# SSFocuser-B-TMC2208-O.net
KiCad netlist of a schematic drawn in Altium Designer
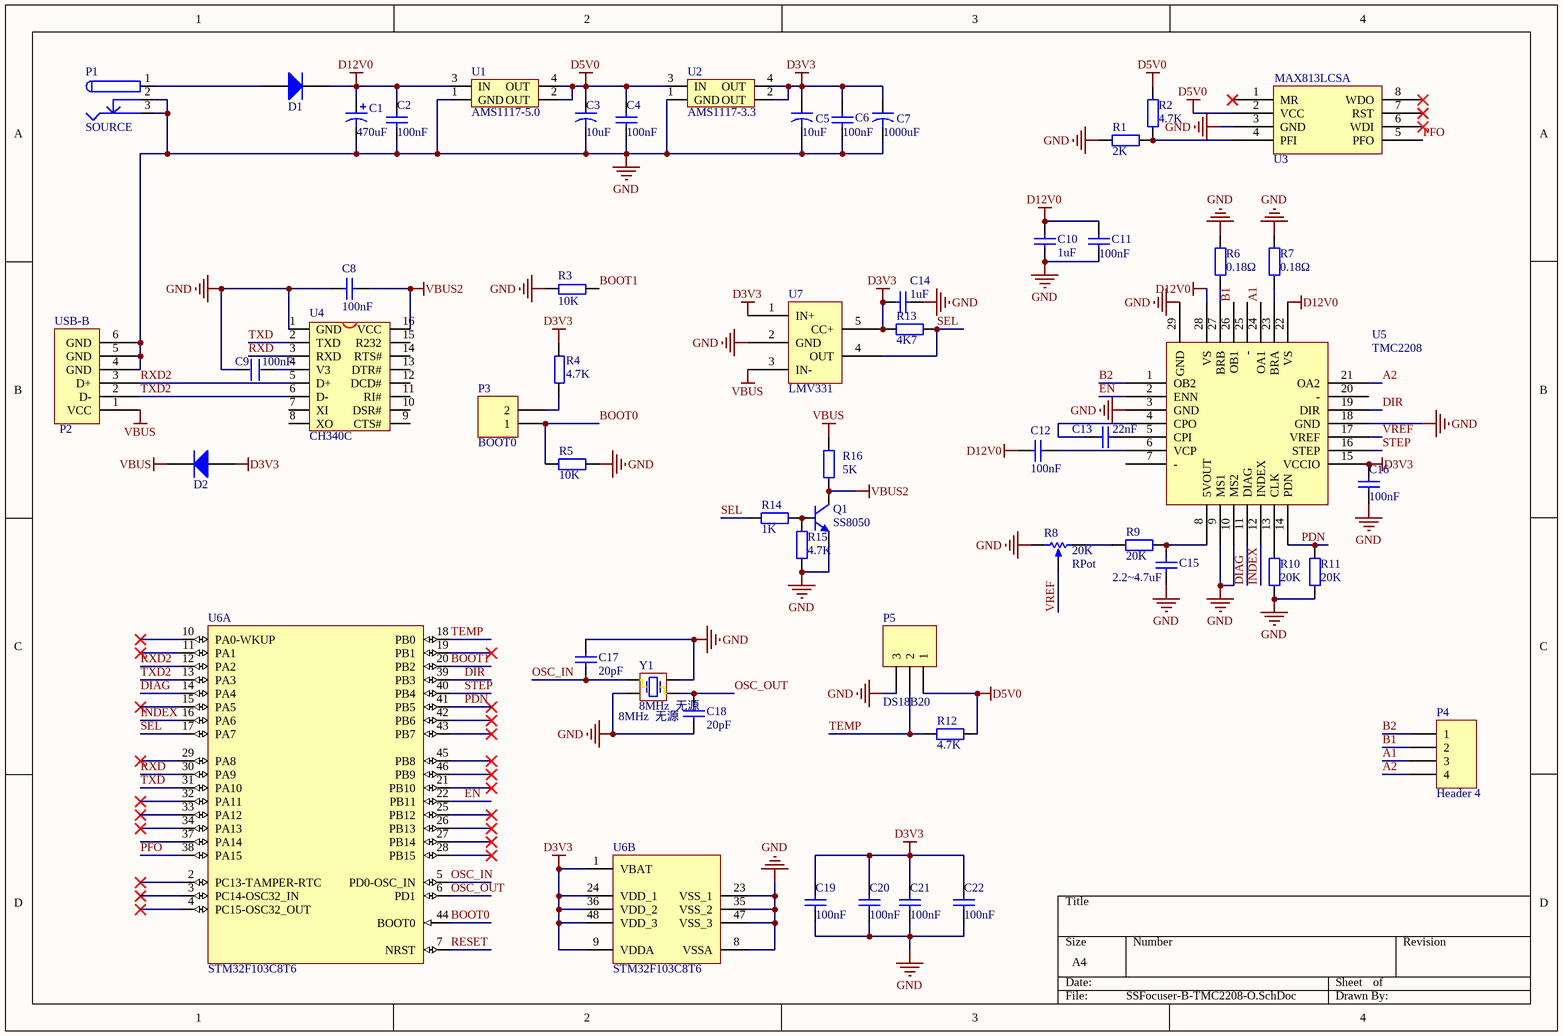
[diagram p0: SSFocuser-B-TMC2208-O.SchDoc]

(export (version "E")
  (design (tool "Eeschema 10.0.6"))
  (components
    (comp (ref "C1")
      (value "470uF")
      (footprint "16V/470U(CD10X10D5)")
      (description "470UF      16V      CD10X10D5")
      (libsource (lib "平台原理图symbol图库V1.0") (part "C470UF016S"))
    )
    (comp (ref "C2")
      (value "100nF")
      (footprint "0603C")
      (description "Capacitor")
      (fields (field (name "PUBLISHER") "Altium Limited"))
      (libsource (lib "Crazy_PCB") (part "Cap"))
    )
    (comp (ref "C3")
      (value "10uF")
      (footprint "3216")
      (fields (field (name "VAULE") "10uF"))
      (libsource (lib "Crazy_PCB") (part "CAP2"))
    )
    (comp (ref "C4")
      (value "100nF")
      (footprint "0603C")
      (description "Capacitor")
      (fields (field (name "PUBLISHER") "Altium Limited"))
      (libsource (lib "Crazy_PCB") (part "Cap"))
    )
    (comp (ref "C5")
      (value "10uF")
      (footprint "3216")
      (fields (field (name "VAULE") "10uF"))
      (libsource (lib "Crazy_PCB") (part "CAP2"))
    )
    (comp (ref "C6")
      (value "100nF")
      (footprint "0603C")
      (description "Capacitor")
      (fields (field (name "PUBLISHER") "Altium Limited"))
      (libsource (lib "Crazy_PCB") (part "Cap"))
    )
    (comp (ref "C7")
      (value "1000uF")
      (footprint "16V/470U(CD10X10D5)")
      (fields (field (name "VAULE") "1000uF"))
      (libsource (lib "Crazy_PCB") (part "CAP2"))
    )
    (comp (ref "C8")
      (value "100nF")
      (footprint "0603C")
      (description "Capacitor")
      (fields (field (name "PUBLISHER") "Altium Limited"))
      (libsource (lib "Crazy_PCB") (part "Cap"))
    )
    (comp (ref "C9")
      (value "100nF")
      (footprint "0603C")
      (libsource (lib "WarShip V3 STM32103封装库") (part "C"))
    )
    (comp (ref "C10")
      (value "1uF")
      (footprint "1206C")
      (description "Capacitor")
      (fields (field (name "PUBLISHER") "Altium Limited"))
      (libsource (lib "Crazy_PCB") (part "Cap"))
    )
    (comp (ref "C11")
      (value "100nF")
      (footprint "0603C")
      (description "Capacitor")
      (fields (field (name "PUBLISHER") "Altium Limited"))
      (libsource (lib "Crazy_PCB") (part "Cap"))
    )
    (comp (ref "C12")
      (value "100nF")
      (footprint "0603C")
      (description "Capacitor")
      (fields (field (name "PUBLISHER") "Altium Limited"))
      (libsource (lib "Crazy_PCB") (part "Cap"))
    )
    (comp (ref "C13")
      (value "22nF")
      (footprint "0603C")
      (description "Capacitor")
      (fields (field (name "PUBLISHER") "Altium Limited"))
      (libsource (lib "Crazy_PCB") (part "Cap"))
    )
    (comp (ref "C14")
      (value "1uF")
      (footprint "0603C")
      (description "Capacitor")
      (fields (field (name "PUBLISHER") "Altium Limited"))
      (libsource (lib "Crazy_PCB") (part "Cap"))
    )
    (comp (ref "C15")
      (value "2.2~4.7uF")
      (footprint "0603C")
      (description "Capacitor")
      (fields (field (name "PUBLISHER") "Altium Limited"))
      (libsource (lib "Crazy_PCB") (part "Cap"))
    )
    (comp (ref "C16")
      (value "100nF")
      (footprint "0603C")
      (description "Capacitor")
      (fields (field (name "PUBLISHER") "Altium Limited"))
      (libsource (lib "Crazy_PCB") (part "Cap"))
    )
    (comp (ref "C17")
      (value "20pF")
      (footprint "0603C")
      (description "Capacitor")
      (fields (field (name "PUBLISHER") "Altium Limited"))
      (libsource (lib "JL_SCH") (part "Cap"))
    )
    (comp (ref "C18")
      (value "20pF")
      (footprint "0603C")
      (description "Capacitor")
      (fields (field (name "PUBLISHER") "Altium Limited"))
      (libsource (lib "JL_SCH") (part "Cap"))
    )
    (comp (ref "C19")
      (value "100nF")
      (footprint "0603C")
      (description "Capacitor")
      (fields (field (name "PUBLISHER") "Altium Limited"))
      (libsource (lib "Crazy_PCB") (part "Cap"))
    )
    (comp (ref "C20")
      (value "100nF")
      (footprint "0603C")
      (description "Capacitor")
      (fields (field (name "PUBLISHER") "Altium Limited"))
      (libsource (lib "Crazy_PCB") (part "Cap"))
    )
    (comp (ref "C21")
      (value "100nF")
      (footprint "0603C")
      (description "Capacitor")
      (fields (field (name "PUBLISHER") "Altium Limited"))
      (libsource (lib "Crazy_PCB") (part "Cap"))
    )
    (comp (ref "C22")
      (value "100nF")
      (footprint "0603C")
      (description "Capacitor")
      (fields (field (name "PUBLISHER") "Altium Limited"))
      (libsource (lib "Crazy_PCB") (part "Cap"))
    )
    (comp (ref "D1")
      (value "M7")
      (footprint "DO-214AC")
      (description "High Conductance Fast Diode")
      (fields (field (name "PUBLISHER") "Altium Limited"))
      (libsource (lib "Crazy_PCB") (part "Diode"))
    )
    (comp (ref "D2")
      (value "M7")
      (footprint "DO-214AC")
      (description "High Conductance Fast Diode")
      (fields (field (name "PUBLISHER") "Altium Limited"))
      (libsource (lib "Crazy_PCB") (part "Diode"))
    )
    (comp (ref "P1")
      (value "SOURCE")
      (footprint "DC005")
      (fields (field (name "PUBLISHER") "Altium Limited"))
      (libsource (lib "Crazy_PCB") (part "SOURCE"))
    )
    (comp (ref "P2") (value "USB-B") (footprint "USB-B") (libsource (lib "DX") (part "USB-B")))
    (comp (ref "P3")
      (value "BOOT0")
      (footprint "HDR1X2")
      (description "Header, 2-Pin")
      (fields (field (name "PUBLISHER") "Altium Limited"))
      (libsource (lib "Miscellaneous Connectors") (part "MHDR1X2"))
    )
    (comp (ref "P4")
      (value "Header 4")
      (footprint "XH_4_V")
      (description "Header, 4-Pin")
      (fields (field (name "PUBLISHER") "Altium Limited"))
      (libsource (lib "Miscellaneous Connectors") (part "Header 4"))
    )
    (comp (ref "P5")
      (value "DS18B20")
      (footprint "TO-92B")
      (description "Header, 3-Pin")
      (fields (field (name "PUBLISHER") "Altium Limited"))
      (libsource (lib "Miscellaneous Connectors") (part "Header 3"))
    )
    (comp (ref "Q1")
      (value "SS8050")
      (footprint "SOT23-3M")
      (description "高频放大-NPN型")
      (fields (field (name "版权归属") "源创客"))
      (libsource (lib "6.2   - 三极管") (part "8050-SMD"))
    )
    (comp (ref "R1")
      (value "2K")
      (footprint "0603R")
      (description "Resistor")
      (fields (field (name "PUBLISHER") "Altium Limited"))
      (libsource (lib "Crazy_PCB") (part "RES"))
    )
    (comp (ref "R2")
      (value "4.7K")
      (footprint "0603R")
      (description "Resistor")
      (fields (field (name "PUBLISHER") "Altium Limited"))
      (libsource (lib "") (part "RES_1"))
    )
    (comp (ref "R3") (value "10K") (footprint "0603R") (libsource (lib "WarShip V3 STM32103封装库") (part "R")))
    (comp (ref "R4") (value "4.7K") (footprint "0603R") (libsource (lib "WarShip V3 STM32103封装库") (part "R")))
    (comp (ref "R5")
      (value "10K")
      (footprint "0603R")
      (description "Resistor")
      (fields (field (name "PUBLISHER") "Altium Limited"))
      (libsource (lib "") (part "RES_2"))
    )
    (comp (ref "R6")
      (value "0.18Ω")
      (footprint "1206R")
      (description "Resistor")
      (fields (field (name "PUBLISHER") "Altium Limited"))
      (libsource (lib "") (part "RES_3"))
    )
    (comp (ref "R7")
      (value "0.18Ω")
      (footprint "1206R")
      (description "Resistor")
      (fields (field (name "PUBLISHER") "Altium Limited"))
      (libsource (lib "") (part "RES_3"))
    )
    (comp (ref "R8")
      (value "RPot")
      (footprint "VR_SMD")
      (description "Potentiometer")
      (fields (field (name "ALTIUM_VALUE") "20K") (field (name "PUBLISHER") "Altium Limited"))
      (libsource (lib "Miscellaneous Devices") (part "RPot"))
    )
    (comp (ref "R9")
      (value "20K")
      (footprint "0603R")
      (description "Resistor")
      (fields (field (name "PUBLISHER") "Altium Limited"))
      (libsource (lib "Crazy_PCB") (part "RES"))
    )
    (comp (ref "R10")
      (value "20K")
      (footprint "0603R")
      (description "Resistor")
      (fields (field (name "PUBLISHER") "Altium Limited"))
      (libsource (lib "") (part "RES_1"))
    )
    (comp (ref "R11")
      (value "20K")
      (footprint "0603R")
      (description "Resistor")
      (fields (field (name "PUBLISHER") "Altium Limited"))
      (libsource (lib "") (part "RES_1"))
    )
    (comp (ref "R12")
      (value "4.7K")
      (footprint "0603R")
      (description "Resistor")
      (fields (field (name "PUBLISHER") "Altium Limited"))
      (libsource (lib "") (part "RES_2"))
    )
    (comp (ref "R13")
      (value "4K7")
      (footprint "0603R")
      (description "Resistor")
      (fields (field (name "PUBLISHER") "Altium Limited"))
      (libsource (lib "Crazy_PCB") (part "RES"))
    )
    (comp (ref "R14")
      (value "1K")
      (footprint "0603R")
      (description "Resistor")
      (fields (field (name "PUBLISHER") "Altium Limited"))
      (libsource (lib "Crazy_PCB") (part "RES"))
    )
    (comp (ref "R15")
      (value "4.7K")
      (footprint "0603R")
      (description "Resistor")
      (fields (field (name "PUBLISHER") "Altium Limited"))
      (libsource (lib "") (part "RES_3"))
    )
    (comp (ref "R16")
      (value "5K")
      (footprint "0603R")
      (description "Resistor")
      (fields (field (name "PUBLISHER") "Altium Limited"))
      (libsource (lib "") (part "RES_3"))
    )
    (comp (ref "U1")
      (value "AMS1117-5.0")
      (footprint "SOT223")
      (libsource (lib "MiniSTM32 V3.0封装库") (part "AMS1117"))
    )
    (comp (ref "U2")
      (value "AMS1117-3.3")
      (footprint "SOT223")
      (libsource (lib "MiniSTM32 V3.0封装库") (part "AMS1117"))
    )
    (comp (ref "U3") (value "MAX813LCSA") (footprint "SOP-8") (libsource (lib "DX") (part "MAX813L")))
    (comp (ref "U4")
      (value "CH340C")
      (footprint "SO-16")
      (description "USB2UART")
      (libsource (lib "WarShip V3 STM32103封装库") (part "CH340G"))
    )
    (comp (ref "U5") (value "TMC2208") (footprint "QFN28") (libsource (lib "SS") (part "TMC2208")))
    (comp (ref "U6")
      (value "STM32F103C8T6")
      (footprint "LQFP48_N")
      (libsource (lib "STMicroelectronics STM32 F1") (part "STM32F103C8T6"))
    )
    (comp (ref "U7")
      (value "LMV331")
      (footprint "SOT-23-5")
      (description "LMV331-SOT23-5")
      (libsource (lib "SS") (part "LMV331"))
    )
    (comp (ref "Y1")
      (value "8MHz  无源")
      (footprint "X3225")
      (description "Crystal Oscillator")
      (fields (field (name "ALTIUM_VALUE") "8MHz  无源") (field (name "PUBLISHER") "Altium Limited"))
      (libsource (lib "JL_SCH") (part "XTAL_1"))
    )
  )
  (nets
    (net (code "1") (name "/A1") (class "Default")
      (node (ref "P4") (pin "3") (pinfunction "3_3") (pintype "passive"))
      (node (ref "U5") (pin "24") (pinfunction "OA1_24") (pintype "passive"))
    )
    (net (code "2") (name "/A2") (class "Default")
      (node (ref "P4") (pin "4") (pinfunction "4_4") (pintype "passive"))
      (node (ref "U5") (pin "21") (pinfunction "OA2_21") (pintype "passive"))
    )
    (net (code "3") (name "/B1") (class "Default")
      (node (ref "P4") (pin "2") (pinfunction "2_2") (pintype "passive"))
      (node (ref "U5") (pin "26") (pinfunction "OB1_26") (pintype "passive"))
    )
    (net (code "4") (name "/B2") (class "Default")
      (node (ref "P4") (pin "1") (pinfunction "1_1") (pintype "passive"))
      (node (ref "U5") (pin "1") (pinfunction "OB2_1") (pintype "passive"))
    )
    (net (code "5") (name "/BOOT0") (class "Default")
      (node (ref "P3") (pin "1") (pinfunction "1_1") (pintype "passive"))
      (node (ref "R5") (pin "1") (pinfunction "1_1") (pintype "passive"))
      (node (ref "U6") (pin "44") (pinfunction "BOOT0_44") (pintype "input"))
    )
    (net (code "6") (name "/BOOT1") (class "Default")
      (node (ref "R3") (pin "2") (pintype "passive"))
      (node (ref "U6") (pin "20") (pinfunction "PB2_20") (pintype "bidirectional"))
    )
    (net (code "7") (name "/DIAG") (class "Default")
      (node (ref "U5") (pin "11") (pinfunction "DIAG_11") (pintype "passive"))
      (node (ref "U6") (pin "14") (pinfunction "PA4_14") (pintype "bidirectional"))
    )
    (net (code "8") (name "/DIR") (class "Default")
      (node (ref "U5") (pin "19") (pinfunction "DIR_19") (pintype "passive"))
      (node (ref "U6") (pin "39") (pinfunction "PB3_39") (pintype "bidirectional"))
    )
    (net (code "9") (name "/EN") (class "Default")
      (node (ref "U5") (pin "2") (pinfunction "ENN_2") (pintype "passive"))
      (node (ref "U6") (pin "22") (pinfunction "PB11_22") (pintype "bidirectional"))
    )
    (net (code "10") (name "/INDEX") (class "Default")
      (node (ref "U5") (pin "12") (pinfunction "INDEX_12") (pintype "passive"))
      (node (ref "U6") (pin "16") (pinfunction "PA6_16") (pintype "bidirectional"))
    )
    (net (code "11") (name "/OSC_IN") (class "Default")
      (node (ref "C17") (pin "1") (pinfunction "1_1") (pintype "passive"))
      (node (ref "U6") (pin "5") (pinfunction "PD0-OSC_IN_5") (pintype "bidirectional"))
      (node (ref "Y1") (pin "1") (pinfunction "OSC1_1") (pintype "passive"))
    )
    (net (code "12") (name "/OSC_OUT") (class "Default")
      (node (ref "C18") (pin "1") (pinfunction "1_1") (pintype "passive"))
      (node (ref "U6") (pin "6") (pinfunction "PD1_6") (pintype "bidirectional"))
      (node (ref "Y1") (pin "3") (pinfunction "OSC2_3") (pintype "passive"))
    )
    (net (code "13") (name "/PDN") (class "Default")
      (node (ref "R11") (pin "2") (pinfunction "2_2") (pintype "passive"))
      (node (ref "U5") (pin "14") (pinfunction "PDN_14") (pintype "passive"))
      (node (ref "U6") (pin "41") (pinfunction "PB5_41") (pintype "bidirectional"))
    )
    (net (code "14") (name "/PFO") (class "Default")
      (node (ref "U3") (pin "5") (pinfunction "PFO_5") (pintype "passive"))
      (node (ref "U6") (pin "38") (pinfunction "PA15_38") (pintype "bidirectional"))
    )
    (net (code "15") (name "/RESET") (class "Default")
      (node (ref "U6") (pin "7") (pinfunction "NRST_7") (pintype "bidirectional"))
    )
    (net (code "16") (name "/RXD") (class "Default")
      (node (ref "U4") (pin "3") (pinfunction "RXD_3") (pintype "passive"))
      (node (ref "U6") (pin "30") (pinfunction "PA9_30") (pintype "bidirectional"))
    )
    (net (code "17") (name "/RXD2") (class "Default")
      (node (ref "P2") (pin "3") (pinfunction "D+_3") (pintype "passive"))
      (node (ref "U4") (pin "5") (pinfunction "D+_5") (pintype "passive"))
      (node (ref "U6") (pin "12") (pinfunction "PA2_12") (pintype "bidirectional"))
    )
    (net (code "18") (name "/SEL") (class "Default")
      (node (ref "R13") (pin "1") (pinfunction "1_1") (pintype "passive"))
      (node (ref "R14") (pin "2") (pinfunction "2_2") (pintype "passive"))
      (node (ref "U6") (pin "17") (pinfunction "PA7_17") (pintype "bidirectional"))
      (node (ref "U7") (pin "4") (pinfunction "OUT_4") (pintype "passive"))
    )
    (net (code "19") (name "/STEP") (class "Default")
      (node (ref "U5") (pin "16") (pinfunction "STEP_16") (pintype "passive"))
      (node (ref "U6") (pin "40") (pinfunction "PB4_40") (pintype "bidirectional"))
    )
    (net (code "20") (name "/TEMP") (class "Default")
      (node (ref "P5") (pin "2") (pinfunction "2_2") (pintype "passive"))
      (node (ref "R12") (pin "1") (pinfunction "1_1") (pintype "passive"))
      (node (ref "U6") (pin "18") (pinfunction "PB0_18") (pintype "bidirectional"))
    )
    (net (code "21") (name "/TXD") (class "Default")
      (node (ref "U4") (pin "2") (pinfunction "TXD_2") (pintype "passive"))
      (node (ref "U6") (pin "31") (pinfunction "PA10_31") (pintype "bidirectional"))
    )
    (net (code "22") (name "/TXD2") (class "Default")
      (node (ref "P2") (pin "2") (pinfunction "D-_2") (pintype "passive"))
      (node (ref "U4") (pin "6") (pinfunction "D-_6") (pintype "passive"))
      (node (ref "U6") (pin "13") (pinfunction "PA3_13") (pintype "bidirectional"))
    )
    (net (code "23") (name "/VREF") (class "Default")
      (node (ref "R8") (pin "3") (pinfunction "TAP_3") (pintype "passive"))
      (node (ref "U5") (pin "17") (pinfunction "VREF_17") (pintype "passive"))
    )
    (net (code "24") (name "D3V3") (class "Default")
      (node (ref "C14") (pin "2") (pinfunction "2_2") (pintype "passive"))
      (node (ref "C16") (pin "2") (pinfunction "2_2") (pintype "passive"))
      (node (ref "C19") (pin "2") (pinfunction "2_2") (pintype "passive"))
      (node (ref "C20") (pin "2") (pinfunction "2_2") (pintype "passive"))
      (node (ref "C21") (pin "2") (pinfunction "2_2") (pintype "passive"))
      (node (ref "C22") (pin "2") (pinfunction "2_2") (pintype "passive"))
      (node (ref "C5") (pin "1") (pinfunction "1_1") (pintype "passive"))
      (node (ref "C6") (pin "2") (pinfunction "2_2") (pintype "passive"))
      (node (ref "C7") (pin "1") (pinfunction "1_1") (pintype "passive"))
      (node (ref "D2") (pin "1") (pinfunction "A_1") (pintype "passive"))
      (node (ref "R13") (pin "2") (pinfunction "2_2") (pintype "passive"))
      (node (ref "R4") (pin "2") (pintype "passive"))
      (node (ref "U2") (pin "2") (pinfunction "OUT_2") (pintype "passive"))
      (node (ref "U2") (pin "4") (pinfunction "OUT_4") (pintype "passive"))
      (node (ref "U5") (pin "15") (pinfunction "VCCIO_15") (pintype "passive"))
      (node (ref "U6") (pin "1") (pinfunction "VBAT_1") (pintype "power_in"))
      (node (ref "U6") (pin "24") (pinfunction "VDD_1_24") (pintype "power_in"))
      (node (ref "U6") (pin "36") (pinfunction "VDD_2_36") (pintype "power_in"))
      (node (ref "U6") (pin "48") (pinfunction "VDD_3_48") (pintype "power_in"))
      (node (ref "U6") (pin "9") (pinfunction "VDDA_9") (pintype "power_in"))
      (node (ref "U7") (pin "1") (pinfunction "IN+_1") (pintype "passive"))
      (node (ref "U7") (pin "5") (pinfunction "CC+_5") (pintype "passive"))
    )
    (net (code "25") (name "D5V0") (class "Default")
      (node (ref "C3") (pin "1") (pinfunction "1_1") (pintype "passive"))
      (node (ref "C4") (pin "2") (pinfunction "2_2") (pintype "passive"))
      (node (ref "P5") (pin "1") (pinfunction "1_1") (pintype "passive"))
      (node (ref "R12") (pin "2") (pinfunction "2_2") (pintype "passive"))
      (node (ref "R2") (pin "2") (pinfunction "2_2") (pintype "passive"))
      (node (ref "U1") (pin "2") (pinfunction "OUT_2") (pintype "passive"))
      (node (ref "U1") (pin "4") (pinfunction "OUT_4") (pintype "passive"))
      (node (ref "U2") (pin "3") (pinfunction "IN_3") (pintype "passive"))
      (node (ref "U3") (pin "2") (pinfunction "VCC_2") (pintype "passive"))
    )
    (net (code "26") (name "D12V0") (class "Default")
      (node (ref "C1") (pin "1") (pinfunction "1_1") (pintype "passive"))
      (node (ref "C10") (pin "1") (pinfunction "1_1") (pintype "passive"))
      (node (ref "C11") (pin "2") (pinfunction "2_2") (pintype "passive"))
      (node (ref "C12") (pin "2") (pinfunction "2_2") (pintype "passive"))
      (node (ref "C2") (pin "2") (pinfunction "2_2") (pintype "passive"))
      (node (ref "D1") (pin "2") (pinfunction "K_2") (pintype "passive"))
      (node (ref "U1") (pin "3") (pinfunction "IN_3") (pintype "passive"))
      (node (ref "U5") (pin "22") (pinfunction "VS_22") (pintype "passive"))
      (node (ref "U5") (pin "28") (pinfunction "VS_28") (pintype "passive"))
    )
    (net (code "27") (name "GND") (class "Default")
      (node (ref "C1") (pin "2") (pinfunction "2_2") (pintype "passive"))
      (node (ref "C10") (pin "2") (pinfunction "2_2") (pintype "passive"))
      (node (ref "C11") (pin "1") (pinfunction "1_1") (pintype "passive"))
      (node (ref "C14") (pin "1") (pinfunction "1_1") (pintype "passive"))
      (node (ref "C15") (pin "1") (pinfunction "1_1") (pintype "passive"))
      (node (ref "C16") (pin "1") (pinfunction "1_1") (pintype "passive"))
      (node (ref "C17") (pin "2") (pinfunction "2_2") (pintype "passive"))
      (node (ref "C18") (pin "2") (pinfunction "2_2") (pintype "passive"))
      (node (ref "C19") (pin "1") (pinfunction "1_1") (pintype "passive"))
      (node (ref "C2") (pin "1") (pinfunction "1_1") (pintype "passive"))
      (node (ref "C20") (pin "1") (pinfunction "1_1") (pintype "passive"))
      (node (ref "C21") (pin "1") (pinfunction "1_1") (pintype "passive"))
      (node (ref "C22") (pin "1") (pinfunction "1_1") (pintype "passive"))
      (node (ref "C3") (pin "2") (pinfunction "2_2") (pintype "passive"))
      (node (ref "C4") (pin "1") (pinfunction "1_1") (pintype "passive"))
      (node (ref "C5") (pin "2") (pinfunction "2_2") (pintype "passive"))
      (node (ref "C6") (pin "1") (pinfunction "1_1") (pintype "passive"))
      (node (ref "C7") (pin "2") (pinfunction "2_2") (pintype "passive"))
      (node (ref "C8") (pin "1") (pinfunction "1_1") (pintype "passive"))
      (node (ref "C9") (pin "1") (pintype "passive"))
      (node (ref "P1") (pin "2") (pinfunction "2_2") (pintype "power_in"))
      (node (ref "P1") (pin "3") (pinfunction "3_3") (pintype "power_in"))
      (node (ref "P2") (pin "4") (pinfunction "GND_4") (pintype "passive"))
      (node (ref "P2") (pin "5") (pinfunction "GND_5") (pintype "passive"))
      (node (ref "P2") (pin "6") (pinfunction "GND_6") (pintype "passive"))
      (node (ref "P5") (pin "3") (pinfunction "3_3") (pintype "passive"))
      (node (ref "Q1") (pin "2") (pinfunction "E_2") (pintype "passive"))
      (node (ref "R1") (pin "2") (pinfunction "2_2") (pintype "passive"))
      (node (ref "R10") (pin "1") (pinfunction "1_1") (pintype "passive"))
      (node (ref "R11") (pin "1") (pinfunction "1_1") (pintype "passive"))
      (node (ref "R15") (pin "2") (pinfunction "2_2") (pintype "passive"))
      (node (ref "R3") (pin "1") (pintype "passive"))
      (node (ref "R5") (pin "2") (pinfunction "2_2") (pintype "passive"))
      (node (ref "R6") (pin "1") (pinfunction "1_1") (pintype "passive"))
      (node (ref "R7") (pin "1") (pinfunction "1_1") (pintype "passive"))
      (node (ref "R8") (pin "1") (pinfunction "TOP_1") (pintype "passive"))
      (node (ref "U1") (pin "1") (pinfunction "GND_1") (pintype "passive"))
      (node (ref "U2") (pin "1") (pinfunction "GND_1") (pintype "passive"))
      (node (ref "U3") (pin "3") (pinfunction "GND_3") (pintype "passive"))
      (node (ref "U4") (pin "1") (pinfunction "GND_1") (pintype "passive"))
      (node (ref "U5") (pin "10") (pinfunction "MS2_10") (pintype "passive"))
      (node (ref "U5") (pin "18") (pinfunction "GND_18") (pintype "passive"))
      (node (ref "U5") (pin "29") (pinfunction "GND_29") (pintype "passive"))
      (node (ref "U5") (pin "3") (pinfunction "GND_3") (pintype "passive"))
      (node (ref "U5") (pin "9") (pinfunction "MS1_9") (pintype "passive"))
      (node (ref "U6") (pin "23") (pinfunction "VSS_1_23") (pintype "power_in"))
      (node (ref "U6") (pin "35") (pinfunction "VSS_2_35") (pintype "power_in"))
      (node (ref "U6") (pin "47") (pinfunction "VSS_3_47") (pintype "power_in"))
      (node (ref "U6") (pin "8") (pinfunction "VSSA_8") (pintype "power_in"))
      (node (ref "U7") (pin "2") (pinfunction "GND_2") (pintype "passive"))
      (node (ref "Y1") (pin "2") (pinfunction "NA_2") (pintype "passive"))
      (node (ref "Y1") (pin "4") (pinfunction "NA_4") (pintype "passive"))
    )
    (net (code "28") (name "Net-(D1-A)") (class "Default")
      (node (ref "D1") (pin "1") (pinfunction "A_1") (pintype "passive"))
      (node (ref "P1") (pin "1") (pinfunction "1_1") (pintype "power_in"))
    )
    (net (code "29") (name "Net-(P3-Pad2)") (class "Default")
      (node (ref "P3") (pin "2") (pinfunction "2_2") (pintype "passive"))
      (node (ref "R4") (pin "1") (pintype "passive"))
    )
    (net (code "30") (name "Net-(Q1-B)") (class "Default")
      (node (ref "Q1") (pin "1") (pinfunction "B_1") (pintype "passive"))
      (node (ref "R14") (pin "1") (pinfunction "1_1") (pintype "passive"))
      (node (ref "R15") (pin "1") (pinfunction "1_1") (pintype "passive"))
    )
    (net (code "31") (name "Net-(R8-BOT)") (class "Default")
      (node (ref "R8") (pin "2") (pinfunction "BOT_2") (pintype "passive"))
      (node (ref "R9") (pin "2") (pinfunction "2_2") (pintype "passive"))
    )
    (net (code "32") (name "Net-(U3-PFI)") (class "Default")
      (node (ref "R1") (pin "1") (pinfunction "1_1") (pintype "passive"))
      (node (ref "R2") (pin "1") (pinfunction "1_1") (pintype "passive"))
      (node (ref "U3") (pin "4") (pinfunction "PFI_4") (pintype "passive"))
    )
    (net (code "33") (name "Net-(U4-V3)") (class "Default")
      (node (ref "C9") (pin "2") (pintype "passive"))
      (node (ref "U4") (pin "4") (pinfunction "V3_4") (pintype "passive"))
    )
    (net (code "34") (name "Net-(U5-5VOUT)") (class "Default")
      (node (ref "C15") (pin "2") (pinfunction "2_2") (pintype "passive"))
      (node (ref "R9") (pin "1") (pinfunction "1_1") (pintype "passive"))
      (node (ref "U5") (pin "8") (pinfunction "5VOUT_8") (pintype "passive"))
    )
    (net (code "35") (name "Net-(U5-BRA)") (class "Default")
      (node (ref "R7") (pin "2") (pinfunction "2_2") (pintype "passive"))
      (node (ref "U5") (pin "23") (pinfunction "BRA_23") (pintype "passive"))
    )
    (net (code "36") (name "Net-(U5-BRB)") (class "Default")
      (node (ref "R6") (pin "2") (pinfunction "2_2") (pintype "passive"))
      (node (ref "U5") (pin "27") (pinfunction "BRB_27") (pintype "passive"))
    )
    (net (code "37") (name "Net-(U5-CLK)") (class "Default")
      (node (ref "R10") (pin "2") (pinfunction "2_2") (pintype "passive"))
      (node (ref "U5") (pin "13") (pinfunction "CLK_13") (pintype "passive"))
    )
    (net (code "38") (name "Net-(U5-CPI)") (class "Default")
      (node (ref "C13") (pin "1") (pinfunction "1_1") (pintype "passive"))
      (node (ref "U5") (pin "5") (pinfunction "CPI_5") (pintype "passive"))
    )
    (net (code "39") (name "Net-(U5-CPO)") (class "Default")
      (node (ref "C13") (pin "2") (pinfunction "2_2") (pintype "passive"))
      (node (ref "U5") (pin "4") (pinfunction "CPO_4") (pintype "passive"))
    )
    (net (code "40") (name "Net-(U5-VCP)") (class "Default")
      (node (ref "C12") (pin "1") (pinfunction "1_1") (pintype "passive"))
      (node (ref "U5") (pin "6") (pinfunction "VCP_6") (pintype "passive"))
    )
    (net (code "41") (name "VBUS") (class "Default")
      (node (ref "D2") (pin "2") (pinfunction "K_2") (pintype "passive"))
      (node (ref "P2") (pin "1") (pinfunction "VCC_1") (pintype "passive"))
      (node (ref "R16") (pin "1") (pinfunction "1_1") (pintype "passive"))
      (node (ref "U7") (pin "3") (pinfunction "IN-_3") (pintype "passive"))
    )
    (net (code "42") (name "VBUS2") (class "Default")
      (node (ref "C8") (pin "2") (pinfunction "2_2") (pintype "passive"))
      (node (ref "Q1") (pin "3") (pinfunction "C_3") (pintype "passive"))
      (node (ref "R16") (pin "2") (pinfunction "2_2") (pintype "passive"))
      (node (ref "U4") (pin "16") (pinfunction "VCC_16") (pintype "passive"))
    )
    (net (code "43") (name "unconnected-(U3-MR-Pad1)") (class "Default")
      (node (ref "U3") (pin "1") (pinfunction "MR_1") (pintype "passive+no_connect"))
    )
    (net (code "44") (name "unconnected-(U3-RST-Pad7)") (class "Default")
      (node (ref "U3") (pin "7") (pinfunction "RST_7") (pintype "passive+no_connect"))
    )
    (net (code "45") (name "unconnected-(U3-WDI-Pad6)") (class "Default")
      (node (ref "U3") (pin "6") (pinfunction "WDI_6") (pintype "passive+no_connect"))
    )
    (net (code "46") (name "unconnected-(U3-WDO-Pad8)") (class "Default")
      (node (ref "U3") (pin "8") (pinfunction "WDO_8") (pintype "passive+no_connect"))
    )
    (net (code "47") (name "unconnected-(U4-CTS#-Pad9)") (class "Default")
      (node (ref "U4") (pin "9") (pinfunction "CTS#_9") (pintype "passive"))
    )
    (net (code "48") (name "unconnected-(U4-DCD#-Pad12)") (class "Default")
      (node (ref "U4") (pin "12") (pinfunction "DCD#_12") (pintype "passive"))
    )
    (net (code "49") (name "unconnected-(U4-DSR#-Pad10)") (class "Default")
      (node (ref "U4") (pin "10") (pinfunction "DSR#_10") (pintype "passive"))
    )
    (net (code "50") (name "unconnected-(U4-DTR#-Pad13)") (class "Default")
      (node (ref "U4") (pin "13") (pinfunction "DTR#_13") (pintype "passive"))
    )
    (net (code "51") (name "unconnected-(U4-R232-Pad15)") (class "Default")
      (node (ref "U4") (pin "15") (pinfunction "R232_15") (pintype "passive"))
    )
    (net (code "52") (name "unconnected-(U4-RI#-Pad11)") (class "Default")
      (node (ref "U4") (pin "11") (pinfunction "RI#_11") (pintype "passive"))
    )
    (net (code "53") (name "unconnected-(U4-RTS#-Pad14)") (class "Default")
      (node (ref "U4") (pin "14") (pinfunction "RTS#_14") (pintype "passive"))
    )
    (net (code "54") (name "unconnected-(U4-XI-Pad7)") (class "Default")
      (node (ref "U4") (pin "7") (pinfunction "XI_7") (pintype "passive"))
    )
    (net (code "55") (name "unconnected-(U4-XO-Pad8)") (class "Default")
      (node (ref "U4") (pin "8") (pinfunction "XO_8") (pintype "passive"))
    )
    (net (code "56") (name "unconnected-(U5---Pad7)") (class "Default")
      (node (ref "U5") (pin "7") (pinfunction "-_7") (pintype "passive"))
    )
    (net (code "57") (name "unconnected-(U5---Pad20)") (class "Default")
      (node (ref "U5") (pin "20") (pinfunction "-_20") (pintype "passive"))
    )
    (net (code "58") (name "unconnected-(U5---Pad25)") (class "Default")
      (node (ref "U5") (pin "25") (pinfunction "-_25") (pintype "passive"))
    )
    (net (code "59") (name "unconnected-(U6A-PA0-WKUP-Pad10)") (class "Default")
      (node (ref "U6") (pin "10") (pinfunction "PA0-WKUP_10") (pintype "bidirectional+no_connect"))
    )
    (net (code "60") (name "unconnected-(U6A-PA1-Pad11)") (class "Default")
      (node (ref "U6") (pin "11") (pinfunction "PA1_11") (pintype "bidirectional+no_connect"))
    )
    (net (code "61") (name "unconnected-(U6A-PA5-Pad15)") (class "Default")
      (node (ref "U6") (pin "15") (pinfunction "PA5_15") (pintype "bidirectional+no_connect"))
    )
    (net (code "62") (name "unconnected-(U6A-PA8-Pad29)") (class "Default")
      (node (ref "U6") (pin "29") (pinfunction "PA8_29") (pintype "bidirectional+no_connect"))
    )
    (net (code "63") (name "unconnected-(U6A-PA11-Pad32)") (class "Default")
      (node (ref "U6") (pin "32") (pinfunction "PA11_32") (pintype "bidirectional+no_connect"))
    )
    (net (code "64") (name "unconnected-(U6A-PA12-Pad33)") (class "Default")
      (node (ref "U6") (pin "33") (pinfunction "PA12_33") (pintype "bidirectional+no_connect"))
    )
    (net (code "65") (name "unconnected-(U6A-PA13-Pad34)") (class "Default")
      (node (ref "U6") (pin "34") (pinfunction "PA13_34") (pintype "bidirectional+no_connect"))
    )
    (net (code "66") (name "unconnected-(U6A-PA14-Pad37)") (class "Default")
      (node (ref "U6") (pin "37") (pinfunction "PA14_37") (pintype "bidirectional"))
    )
    (net (code "67") (name "unconnected-(U6A-PB1-Pad19)") (class "Default")
      (node (ref "U6") (pin "19") (pinfunction "PB1_19") (pintype "bidirectional+no_connect"))
    )
    (net (code "68") (name "unconnected-(U6A-PB6-Pad42)") (class "Default")
      (node (ref "U6") (pin "42") (pinfunction "PB6_42") (pintype "bidirectional+no_connect"))
    )
    (net (code "69") (name "unconnected-(U6A-PB7-Pad43)") (class "Default")
      (node (ref "U6") (pin "43") (pinfunction "PB7_43") (pintype "bidirectional+no_connect"))
    )
    (net (code "70") (name "unconnected-(U6A-PB8-Pad45)") (class "Default")
      (node (ref "U6") (pin "45") (pinfunction "PB8_45") (pintype "bidirectional+no_connect"))
    )
    (net (code "71") (name "unconnected-(U6A-PB9-Pad46)") (class "Default")
      (node (ref "U6") (pin "46") (pinfunction "PB9_46") (pintype "bidirectional+no_connect"))
    )
    (net (code "72") (name "unconnected-(U6A-PB10-Pad21)") (class "Default")
      (node (ref "U6") (pin "21") (pinfunction "PB10_21") (pintype "bidirectional+no_connect"))
    )
    (net (code "73") (name "unconnected-(U6A-PB12-Pad25)") (class "Default")
      (node (ref "U6") (pin "25") (pinfunction "PB12_25") (pintype "bidirectional+no_connect"))
    )
    (net (code "74") (name "unconnected-(U6A-PB13-Pad26)") (class "Default")
      (node (ref "U6") (pin "26") (pinfunction "PB13_26") (pintype "bidirectional+no_connect"))
    )
    (net (code "75") (name "unconnected-(U6A-PB14-Pad27)") (class "Default")
      (node (ref "U6") (pin "27") (pinfunction "PB14_27") (pintype "bidirectional+no_connect"))
    )
    (net (code "76") (name "unconnected-(U6A-PB15-Pad28)") (class "Default")
      (node (ref "U6") (pin "28") (pinfunction "PB15_28") (pintype "bidirectional+no_connect"))
    )
    (net (code "77") (name "unconnected-(U6A-PC13-TAMPER-RTC-Pad2)") (class "Default")
      (node (ref "U6") (pin "2") (pinfunction "PC13-TAMPER-RTC_2") (pintype "bidirectional+no_connect"))
    )
    (net (code "78") (name "unconnected-(U6A-PC14-OSC32_IN-Pad3)") (class "Default")
      (node (ref "U6") (pin "3") (pinfunction "PC14-OSC32_IN_3") (pintype "bidirectional+no_connect"))
    )
    (net (code "79") (name "unconnected-(U6A-PC15-OSC32_OUT-Pad4)") (class "Default")
      (node (ref "U6") (pin "4") (pinfunction "PC15-OSC32_OUT_4") (pintype "bidirectional+no_connect"))
    )
  )
)
